# sd-card-male.net
KiCad netlist of a schematic drawn in EAGLE
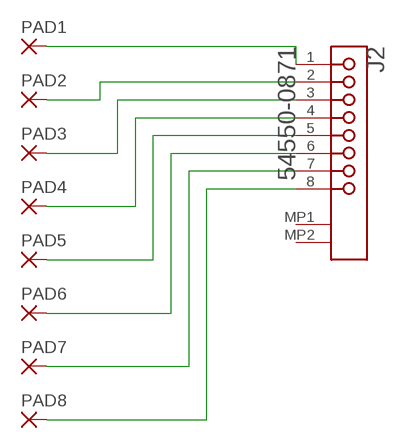
[diagram p0: schematic, sheet 1]

(export (version "E")
  (design (tool "Eeschema 10.0.6"))
  (components
    (comp (ref "J2")
      (value "MOLEX_54550-0871MOLEX_54550-0871_0_0")
      (footprint "eagle-import:MOLEX_54550-0871_0")
      (fields (field (name "MF") "Molex") (field (name "MPN") "54550-0871"))
      (libsource (lib "eagle-import") (part "MOLEX_54550-0871MOLEX_54550-0871_0_0"))
    )
    (comp (ref "PAD1")
      (value "SD_PAD_SMD_SHORT")
      (footprint "eagle-import:SD_PAD_SMD_SHORT")
      (libsource (lib "eagle-import") (part "SD_PAD_SMD_SHORT"))
    )
    (comp (ref "PAD2")
      (value "SD_PAD_SMD_SHORT")
      (footprint "eagle-import:SD_PAD_SMD_SHORT")
      (libsource (lib "eagle-import") (part "SD_PAD_SMD_SHORT"))
    )
    (comp (ref "PAD3")
      (value "SD_PAD_SMD_SHORT")
      (footprint "eagle-import:SD_PAD_SMD_SHORT")
      (libsource (lib "eagle-import") (part "SD_PAD_SMD_SHORT"))
    )
    (comp (ref "PAD4")
      (value "SD_PAD_SMD_LONG")
      (footprint "eagle-import:SD_PAD_SMD_LONG")
      (libsource (lib "eagle-import") (part "SD_PAD_SMD_LONG"))
    )
    (comp (ref "PAD5")
      (value "SD_PAD_SMD_SHORT")
      (footprint "eagle-import:SD_PAD_SMD_SHORT")
      (libsource (lib "eagle-import") (part "SD_PAD_SMD_SHORT"))
    )
    (comp (ref "PAD6")
      (value "SD_PAD_SMD_LONG")
      (footprint "eagle-import:SD_PAD_SMD_LONG")
      (libsource (lib "eagle-import") (part "SD_PAD_SMD_LONG"))
    )
    (comp (ref "PAD7")
      (value "SD_PAD_SMD_SHORT")
      (footprint "eagle-import:SD_PAD_SMD_SHORT")
      (libsource (lib "eagle-import") (part "SD_PAD_SMD_SHORT"))
    )
    (comp (ref "PAD8")
      (value "SD_PAD_SMD_SHORT")
      (footprint "eagle-import:SD_PAD_SMD_SHORT")
      (libsource (lib "eagle-import") (part "SD_PAD_SMD_SHORT"))
    )
  )
  (nets
    (net (code "1") (name "Net-(PAD1-P)") (class "Default")
      (node (ref "J2") (pin "1") (pinfunction "1_1") (pintype "passive"))
      (node (ref "PAD1") (pin "1") (pinfunction "P_1") (pintype "passive"))
    )
    (net (code "2") (name "Net-(PAD2-P)") (class "Default")
      (node (ref "J2") (pin "2") (pinfunction "2_2") (pintype "passive"))
      (node (ref "PAD2") (pin "1") (pinfunction "P_1") (pintype "passive"))
    )
    (net (code "3") (name "Net-(PAD3-P)") (class "Default")
      (node (ref "J2") (pin "3") (pinfunction "3_3") (pintype "passive"))
      (node (ref "PAD3") (pin "1") (pinfunction "P_1") (pintype "passive"))
    )
    (net (code "4") (name "Net-(PAD4-P)") (class "Default")
      (node (ref "J2") (pin "4") (pinfunction "4_4") (pintype "passive"))
      (node (ref "PAD4") (pin "1") (pinfunction "P_1") (pintype "passive"))
    )
    (net (code "5") (name "Net-(PAD5-P)") (class "Default")
      (node (ref "J2") (pin "5") (pinfunction "5_5") (pintype "passive"))
      (node (ref "PAD5") (pin "1") (pinfunction "P_1") (pintype "passive"))
    )
    (net (code "6") (name "Net-(PAD6-P)") (class "Default")
      (node (ref "J2") (pin "6") (pinfunction "6_6") (pintype "passive"))
      (node (ref "PAD6") (pin "1") (pinfunction "P_1") (pintype "passive"))
    )
    (net (code "7") (name "Net-(PAD7-P)") (class "Default")
      (node (ref "J2") (pin "7") (pinfunction "7_7") (pintype "passive"))
      (node (ref "PAD7") (pin "1") (pinfunction "P_1") (pintype "passive"))
    )
    (net (code "8") (name "Net-(PAD8-P)") (class "Default")
      (node (ref "J2") (pin "8") (pinfunction "8_8") (pintype "passive"))
      (node (ref "PAD8") (pin "1") (pinfunction "P_1") (pintype "passive"))
    )
    (net (code "9") (name "unconnected-(J2-PadMP1)") (class "Default")
      (node (ref "J2") (pin "MP1") (pinfunction "MP1_MP1") (pintype "passive"))
    )
    (net (code "10") (name "unconnected-(J2-PadMP2)") (class "Default")
      (node (ref "J2") (pin "MP2") (pinfunction "MP2_MP2") (pintype "passive"))
    )
  )
)
